# Gustav_M_sensor_board.net
KiCad netlist of a schematic drawn in EAGLE
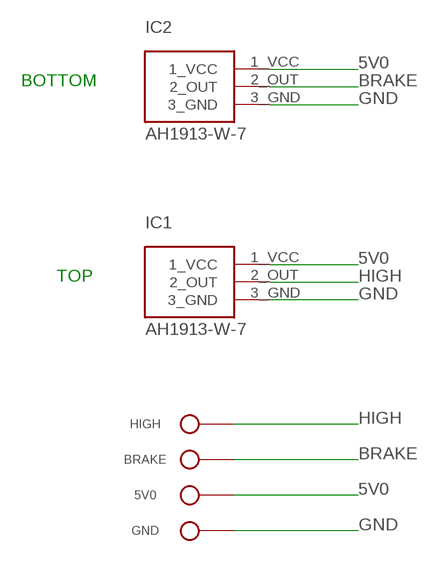
[diagram p0: schematic, sheet 1]

(export (version "E")
  (design (tool "Eeschema 10.0.6"))
  (components
    (comp (ref "5V0")
      (value "8V4 Battery +")
      (footprint "eagle-import:TH-0.9MM")
      (libsource (lib "eagle-import") (part "TPTH-0.9MM"))
    )
    (comp (ref "BRAKE")
      (value "8V4 Battery +")
      (footprint "eagle-import:TH-0.9MM")
      (libsource (lib "eagle-import") (part "TPTH-0.9MM"))
    )
    (comp (ref "GND")
      (value "8V4 Battery +")
      (footprint "eagle-import:TH-0.9MM")
      (libsource (lib "eagle-import") (part "TPTH-0.9MM"))
    )
    (comp (ref "HIGH")
      (value "8V4 Battery +")
      (footprint "eagle-import:TH-0.9MM")
      (libsource (lib "eagle-import") (part "TPTH-0.9MM"))
    )
    (comp (ref "IC1")
      (value "AH1913-W-7")
      (footprint "eagle-import:SC59-3")
      (libsource (lib "eagle-import") (part "AD1913"))
    )
    (comp (ref "IC2")
      (value "AH1913-W-7")
      (footprint "eagle-import:SC59-3")
      (libsource (lib "eagle-import") (part "AD1913"))
    )
  )
  (nets
    (net (code "1") (name "/5V0") (class "Default")
      (node (ref "5V0") (pin "TP$1") (pinfunction "TP$1_TP$1") (pintype "bidirectional"))
      (node (ref "IC1") (pin "1_VCC") (pinfunction "1_VCC_1_VCC") (pintype "power_in"))
      (node (ref "IC2") (pin "1_VCC") (pinfunction "1_VCC_1_VCC") (pintype "power_in"))
    )
    (net (code "2") (name "/BRAKE") (class "Default")
      (node (ref "BRAKE") (pin "TP$1") (pinfunction "TP$1_TP$1") (pintype "bidirectional"))
      (node (ref "IC2") (pin "2_OUT") (pinfunction "2_OUT_2_OUT") (pintype "output"))
    )
    (net (code "3") (name "/GND") (class "Default")
      (node (ref "GND") (pin "TP$1") (pinfunction "TP$1_TP$1") (pintype "bidirectional"))
      (node (ref "IC1") (pin "3_GND") (pinfunction "3_GND_3_GND") (pintype "power_in"))
      (node (ref "IC2") (pin "3_GND") (pinfunction "3_GND_3_GND") (pintype "power_in"))
    )
    (net (code "4") (name "/HIGH") (class "Default")
      (node (ref "HIGH") (pin "TP$1") (pinfunction "TP$1_TP$1") (pintype "bidirectional"))
      (node (ref "IC1") (pin "2_OUT") (pinfunction "2_OUT_2_OUT") (pintype "output"))
    )
  )
)
